# giraffevolvo.net
KiCad netlist of a schematic drawn in EAGLE
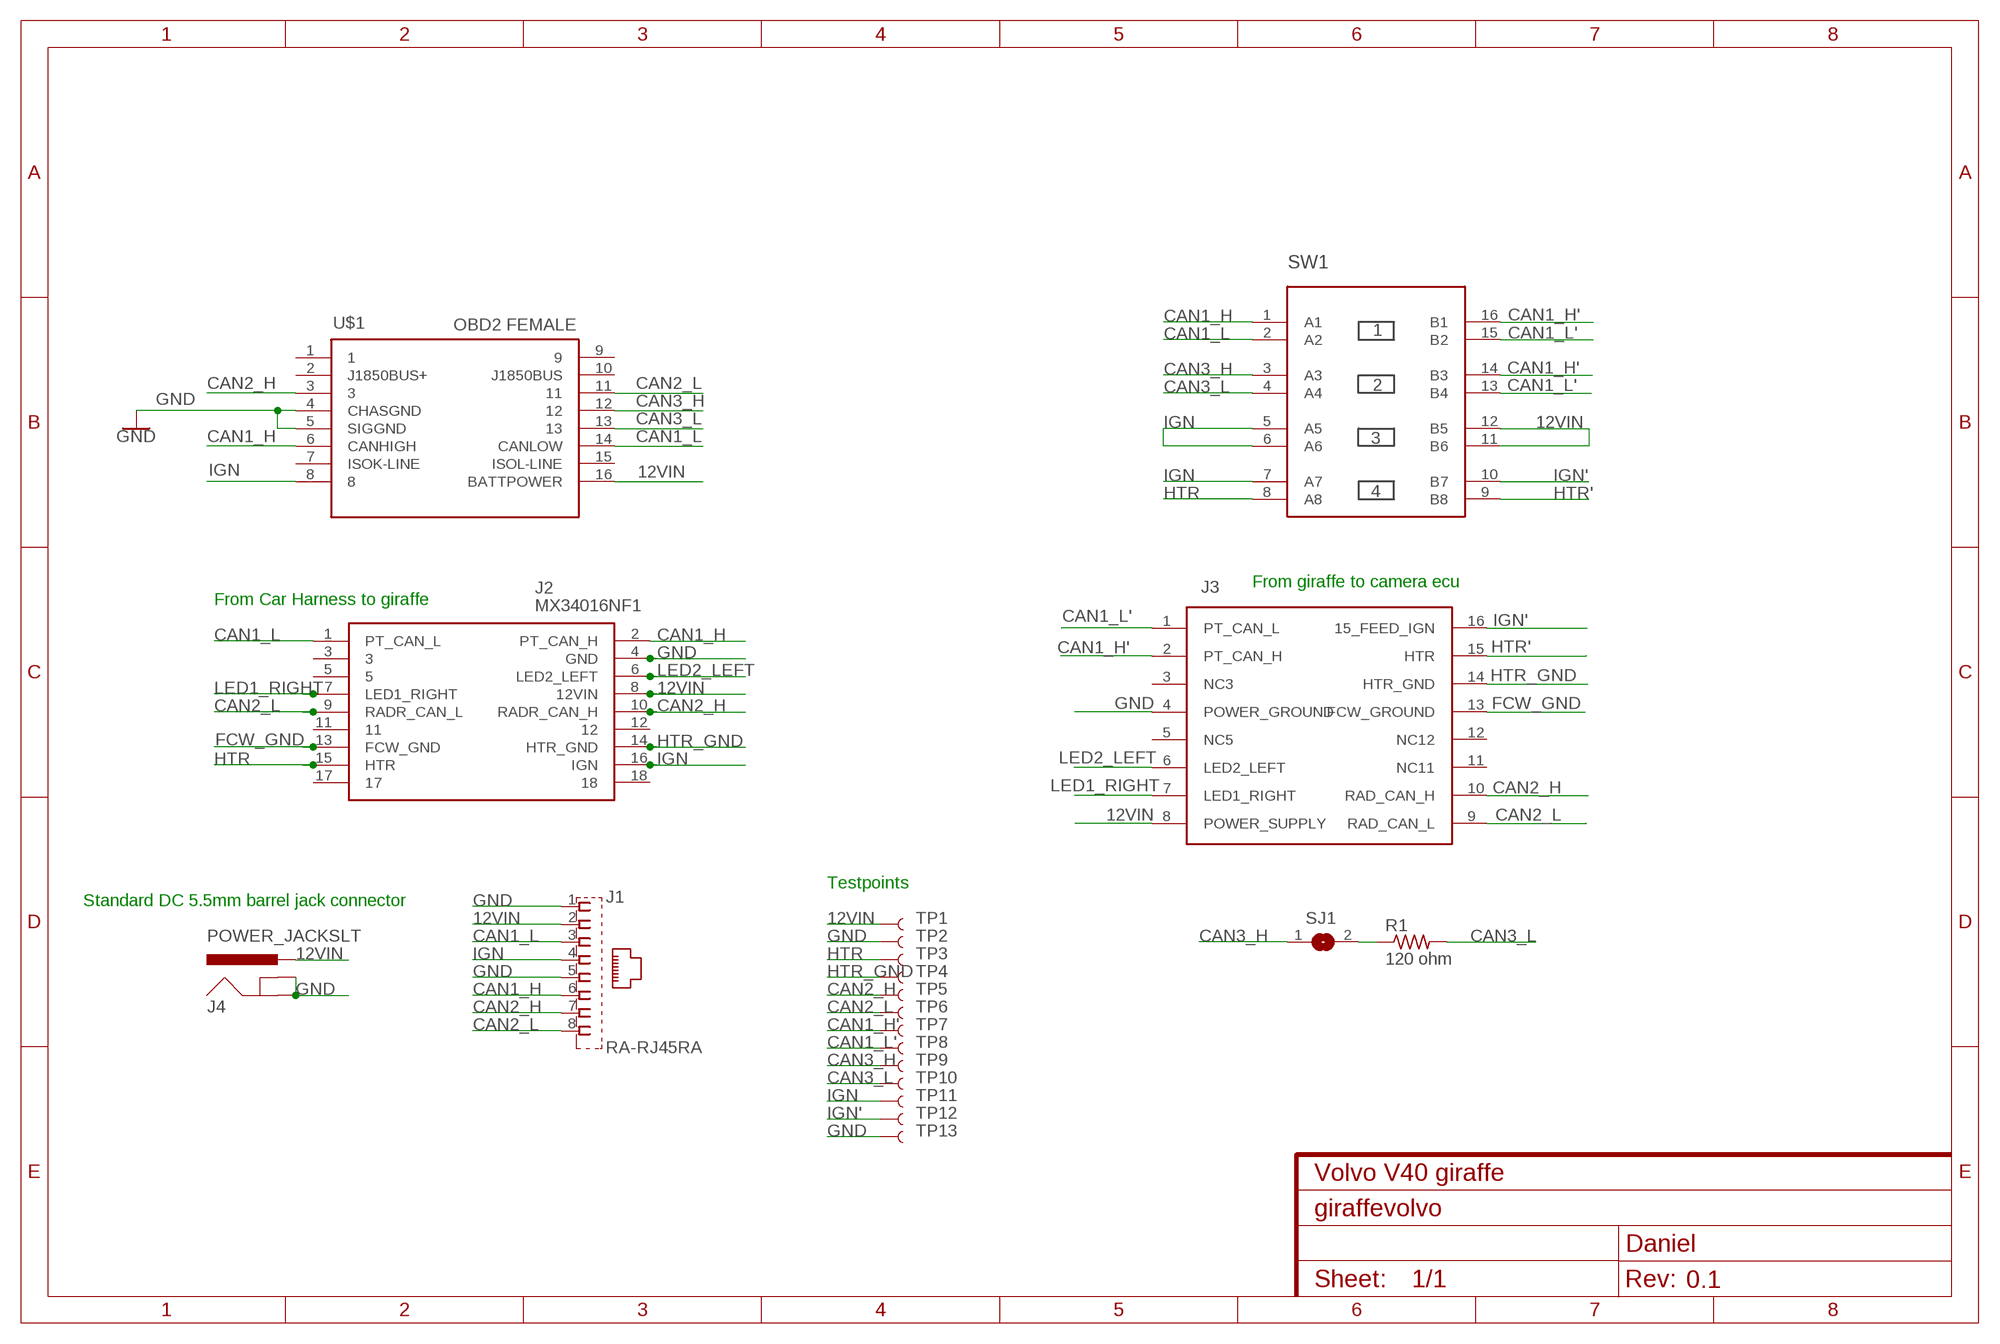
[diagram p0: schematic, sheet 1]

(export (version "E")
  (design (tool "Eeschema 10.0.6"))
  (components
    (comp (ref "J1")
      (value "RA-RJ45RA")
      (footprint "eagle-import:RA-RJ45")
      (libsource (lib "eagle-import") (part "RA-RJ45RA"))
    )
    (comp (ref "J2")
      (value "MX34016NF1")
      (footprint "eagle-import:MX34016NF1")
      (fields (field (name "MOUSER_PART_NUMBER") "656-MX34016NF1"))
      (libsource (lib "eagle-import") (part "MX34016NF1"))
    )
    (comp (ref "J3")
      (value "MX34016SF1")
      (footprint "eagle-import:MX34016SF1")
      (libsource (lib "eagle-import") (part "MX34016SF1"))
    )
    (comp (ref "J4")
      (value "POWER_JACKSLT")
      (footprint "eagle-import:POWER_JACK_SLOT")
      (libsource (lib "eagle-import") (part "POWER_JACKSLT"))
    )
    (comp (ref "R1")
      (value "120 ohm")
      (footprint "eagle-import:0603-R")
      (libsource (lib "eagle-import") (part "R0603"))
    )
    (comp (ref "SJ1") (value "SJ") (footprint "eagle-import:SJ") (libsource (lib "eagle-import") (part "SJ")))
    (comp (ref "SW1")
      (value "4XDPSTSMT")
      (footprint "eagle-import:4-DPST")
      (libsource (lib "eagle-import") (part "4XDPSTSMT"))
    )
    (comp (ref "TP1")
      (value "TEST-POINT2")
      (footprint "eagle-import:PAD.02X.02")
      (libsource (lib "eagle-import") (part "TEST-POINT2"))
    )
    (comp (ref "TP2")
      (value "TEST-POINT2")
      (footprint "eagle-import:PAD.02X.02")
      (libsource (lib "eagle-import") (part "TEST-POINT2"))
    )
    (comp (ref "TP3")
      (value "TEST-POINT2")
      (footprint "eagle-import:PAD.02X.02")
      (libsource (lib "eagle-import") (part "TEST-POINT2"))
    )
    (comp (ref "TP4")
      (value "TEST-POINT2")
      (footprint "eagle-import:PAD.02X.02")
      (libsource (lib "eagle-import") (part "TEST-POINT2"))
    )
    (comp (ref "TP5")
      (value "TEST-POINT2")
      (footprint "eagle-import:PAD.02X.02")
      (libsource (lib "eagle-import") (part "TEST-POINT2"))
    )
    (comp (ref "TP6")
      (value "TEST-POINT2")
      (footprint "eagle-import:PAD.02X.02")
      (libsource (lib "eagle-import") (part "TEST-POINT2"))
    )
    (comp (ref "TP7")
      (value "TEST-POINT2")
      (footprint "eagle-import:PAD.02X.02")
      (libsource (lib "eagle-import") (part "TEST-POINT2"))
    )
    (comp (ref "TP8")
      (value "TEST-POINT2")
      (footprint "eagle-import:PAD.02X.02")
      (libsource (lib "eagle-import") (part "TEST-POINT2"))
    )
    (comp (ref "TP9")
      (value "TEST-POINT2")
      (footprint "eagle-import:PAD.02X.02")
      (libsource (lib "eagle-import") (part "TEST-POINT2"))
    )
    (comp (ref "TP10")
      (value "TEST-POINT2")
      (footprint "eagle-import:PAD.02X.02")
      (libsource (lib "eagle-import") (part "TEST-POINT2"))
    )
    (comp (ref "TP11")
      (value "TEST-POINT2")
      (footprint "eagle-import:PAD.02X.02")
      (libsource (lib "eagle-import") (part "TEST-POINT2"))
    )
    (comp (ref "TP12")
      (value "TEST-POINT2")
      (footprint "eagle-import:PAD.02X.02")
      (libsource (lib "eagle-import") (part "TEST-POINT2"))
    )
    (comp (ref "TP13")
      (value "TEST-POINT2")
      (footprint "eagle-import:PAD.02X.02")
      (libsource (lib "eagle-import") (part "TEST-POINT2"))
    )
    (comp (ref "U$1")
      (value "OBDIIFEMALE")
      (footprint "eagle-import:OBDII-FEMALE")
      (fields (field (name "TEXT") "OBD2 FEMALE  "))
      (libsource (lib "eagle-import") (part "OBDIIFEMALE"))
    )
  )
  (nets
    (net (code "1") (name "/12VIN") (class "Default")
      (node (ref "J1") (pin "2") (pinfunction "2_2") (pintype "passive"))
      (node (ref "J2") (pin "8") (pinfunction "12VIN_8") (pintype "bidirectional"))
      (node (ref "J3") (pin "8") (pinfunction "POWER_SUPPLY_8") (pintype "power_in"))
      (node (ref "J4") (pin "PWR") (pinfunction "PWR_PWR") (pintype "bidirectional"))
      (node (ref "SW1") (pin "11") (pinfunction "B6_11") (pintype "bidirectional"))
      (node (ref "SW1") (pin "12") (pinfunction "B5_12") (pintype "bidirectional"))
      (node (ref "TP1") (pin "P$1") (pinfunction "1_P$1") (pintype "bidirectional"))
      (node (ref "U$1") (pin "16") (pinfunction "BATTPOWER_16") (pintype "bidirectional"))
    )
    (net (code "2") (name "/CAN1_H") (class "Default")
      (node (ref "J1") (pin "6") (pinfunction "6_6") (pintype "passive"))
      (node (ref "J2") (pin "2") (pinfunction "PT_CAN_H_2") (pintype "bidirectional"))
      (node (ref "SW1") (pin "1") (pinfunction "A1_1") (pintype "bidirectional"))
      (node (ref "U$1") (pin "6") (pinfunction "CANHIGH_6") (pintype "bidirectional"))
    )
    (net (code "3") (name "/CAN1_H'") (class "Default")
      (node (ref "J3") (pin "2") (pinfunction "PT_CAN_H_2") (pintype "bidirectional"))
      (node (ref "SW1") (pin "14") (pinfunction "B3_14") (pintype "bidirectional"))
      (node (ref "SW1") (pin "16") (pinfunction "B1_16") (pintype "bidirectional"))
      (node (ref "TP7") (pin "P$1") (pinfunction "1_P$1") (pintype "bidirectional"))
    )
    (net (code "4") (name "/CAN1_L") (class "Default")
      (node (ref "J1") (pin "3") (pinfunction "3_3") (pintype "passive"))
      (node (ref "J2") (pin "1") (pinfunction "PT_CAN_L_1") (pintype "bidirectional"))
      (node (ref "SW1") (pin "2") (pinfunction "A2_2") (pintype "bidirectional"))
      (node (ref "U$1") (pin "14") (pinfunction "CANLOW_14") (pintype "bidirectional"))
    )
    (net (code "5") (name "/CAN1_L'") (class "Default")
      (node (ref "J3") (pin "1") (pinfunction "PT_CAN_L_1") (pintype "bidirectional"))
      (node (ref "SW1") (pin "13") (pinfunction "B4_13") (pintype "bidirectional"))
      (node (ref "SW1") (pin "15") (pinfunction "B2_15") (pintype "bidirectional"))
      (node (ref "TP8") (pin "P$1") (pinfunction "1_P$1") (pintype "bidirectional"))
    )
    (net (code "6") (name "/CAN2_H") (class "Default")
      (node (ref "J1") (pin "7") (pinfunction "7_7") (pintype "passive"))
      (node (ref "J2") (pin "10") (pinfunction "RADR_CAN_H_10") (pintype "bidirectional"))
      (node (ref "J3") (pin "10") (pinfunction "RAD_CAN_H_10") (pintype "bidirectional"))
      (node (ref "TP5") (pin "P$1") (pinfunction "1_P$1") (pintype "bidirectional"))
      (node (ref "U$1") (pin "3") (pinfunction "3_3") (pintype "bidirectional"))
    )
    (net (code "7") (name "/CAN2_L") (class "Default")
      (node (ref "J1") (pin "8") (pinfunction "8_8") (pintype "passive"))
      (node (ref "J2") (pin "9") (pinfunction "RADR_CAN_L_9") (pintype "bidirectional"))
      (node (ref "J3") (pin "9") (pinfunction "RAD_CAN_L_9") (pintype "bidirectional"))
      (node (ref "TP6") (pin "P$1") (pinfunction "1_P$1") (pintype "bidirectional"))
      (node (ref "U$1") (pin "11") (pinfunction "11_11") (pintype "bidirectional"))
    )
    (net (code "8") (name "/CAN3_H") (class "Default")
      (node (ref "SJ1") (pin "1") (pinfunction "1_1") (pintype "passive"))
      (node (ref "SW1") (pin "3") (pinfunction "A3_3") (pintype "bidirectional"))
      (node (ref "TP9") (pin "P$1") (pinfunction "1_P$1") (pintype "bidirectional"))
      (node (ref "U$1") (pin "12") (pinfunction "12_12") (pintype "bidirectional"))
    )
    (net (code "9") (name "/CAN3_L") (class "Default")
      (node (ref "R1") (pin "2") (pinfunction "2_2") (pintype "passive"))
      (node (ref "SW1") (pin "4") (pinfunction "A4_4") (pintype "bidirectional"))
      (node (ref "TP10") (pin "P$1") (pinfunction "1_P$1") (pintype "bidirectional"))
      (node (ref "U$1") (pin "13") (pinfunction "13_13") (pintype "bidirectional"))
    )
    (net (code "10") (name "/FCW_GND") (class "Default")
      (node (ref "J2") (pin "13") (pinfunction "FCW_GND_13") (pintype "bidirectional"))
      (node (ref "J3") (pin "13") (pinfunction "FCW_GROUND_13") (pintype "bidirectional"))
    )
    (net (code "11") (name "/HTR") (class "Default")
      (node (ref "J2") (pin "15") (pinfunction "HTR_15") (pintype "bidirectional"))
      (node (ref "SW1") (pin "8") (pinfunction "A8_8") (pintype "bidirectional"))
      (node (ref "TP3") (pin "P$1") (pinfunction "1_P$1") (pintype "bidirectional"))
    )
    (net (code "12") (name "/HTR'") (class "Default")
      (node (ref "J3") (pin "15") (pinfunction "HTR_15") (pintype "bidirectional"))
      (node (ref "SW1") (pin "9") (pinfunction "B8_9") (pintype "bidirectional"))
    )
    (net (code "13") (name "/HTR_GND") (class "Default")
      (node (ref "J2") (pin "14") (pinfunction "HTR_GND_14") (pintype "bidirectional"))
      (node (ref "J3") (pin "14") (pinfunction "HTR_GND_14") (pintype "bidirectional"))
      (node (ref "TP4") (pin "P$1") (pinfunction "1_P$1") (pintype "bidirectional"))
    )
    (net (code "14") (name "/IGN") (class "Default")
      (node (ref "J1") (pin "4") (pinfunction "4_4") (pintype "passive"))
      (node (ref "J2") (pin "16") (pinfunction "IGN_16") (pintype "bidirectional"))
      (node (ref "SW1") (pin "5") (pinfunction "A5_5") (pintype "bidirectional"))
      (node (ref "SW1") (pin "6") (pinfunction "A6_6") (pintype "bidirectional"))
      (node (ref "SW1") (pin "7") (pinfunction "A7_7") (pintype "bidirectional"))
      (node (ref "TP11") (pin "P$1") (pinfunction "1_P$1") (pintype "bidirectional"))
      (node (ref "U$1") (pin "8") (pinfunction "8_8") (pintype "bidirectional"))
    )
    (net (code "15") (name "/IGN'") (class "Default")
      (node (ref "J3") (pin "16") (pinfunction "15_FEED_IGN_16") (pintype "bidirectional"))
      (node (ref "SW1") (pin "10") (pinfunction "B7_10") (pintype "bidirectional"))
      (node (ref "TP12") (pin "P$1") (pinfunction "1_P$1") (pintype "bidirectional"))
    )
    (net (code "16") (name "/LED1_RIGHT") (class "Default")
      (node (ref "J2") (pin "7") (pinfunction "LED1_RIGHT_7") (pintype "bidirectional"))
      (node (ref "J3") (pin "7") (pinfunction "LED1_RIGHT_7") (pintype "bidirectional"))
    )
    (net (code "17") (name "/LED2_LEFT") (class "Default")
      (node (ref "J2") (pin "6") (pinfunction "LED2_LEFT_6") (pintype "bidirectional"))
      (node (ref "J3") (pin "6") (pinfunction "LED2_LEFT_6") (pintype "bidirectional"))
    )
    (net (code "18") (name "GND") (class "Default")
      (node (ref "J1") (pin "1") (pinfunction "1_1") (pintype "passive"))
      (node (ref "J1") (pin "5") (pinfunction "5_5") (pintype "passive"))
      (node (ref "J2") (pin "4") (pinfunction "GND_4") (pintype "bidirectional"))
      (node (ref "J3") (pin "4") (pinfunction "POWER_GROUND_4") (pintype "bidirectional"))
      (node (ref "J4") (pin "GND@1") (pinfunction "GNDBREAK_GND@1") (pintype "bidirectional"))
      (node (ref "J4") (pin "GND@2") (pinfunction "GND_GND@2") (pintype "bidirectional"))
      (node (ref "TP13") (pin "P$1") (pinfunction "1_P$1") (pintype "bidirectional"))
      (node (ref "TP2") (pin "P$1") (pinfunction "1_P$1") (pintype "bidirectional"))
      (node (ref "U$1") (pin "4") (pinfunction "CHASGND_4") (pintype "bidirectional"))
      (node (ref "U$1") (pin "5") (pinfunction "SIGGND_5") (pintype "bidirectional"))
    )
    (net (code "19") (name "Net-(R1-Pad1)") (class "Default")
      (node (ref "R1") (pin "1") (pinfunction "1_1") (pintype "passive"))
      (node (ref "SJ1") (pin "2") (pinfunction "2_2") (pintype "passive"))
    )
    (net (code "20") (name "unconnected-(J2-Pad3)") (class "Default")
      (node (ref "J2") (pin "3") (pinfunction "3_3") (pintype "no_connect"))
    )
    (net (code "21") (name "unconnected-(J2-Pad5)") (class "Default")
      (node (ref "J2") (pin "5") (pinfunction "5_5") (pintype "no_connect"))
    )
    (net (code "22") (name "unconnected-(J2-Pad11)") (class "Default")
      (node (ref "J2") (pin "11") (pinfunction "11_11") (pintype "no_connect"))
    )
    (net (code "23") (name "unconnected-(J2-Pad12)") (class "Default")
      (node (ref "J2") (pin "12") (pinfunction "12_12") (pintype "no_connect"))
    )
    (net (code "24") (name "unconnected-(J2-Pad17)") (class "Default")
      (node (ref "J2") (pin "17") (pinfunction "17_17") (pintype "no_connect"))
    )
    (net (code "25") (name "unconnected-(J2-Pad18)") (class "Default")
      (node (ref "J2") (pin "18") (pinfunction "18_18") (pintype "no_connect"))
    )
    (net (code "26") (name "unconnected-(J3-NC3-Pad3)") (class "Default")
      (node (ref "J3") (pin "3") (pinfunction "NC3_3") (pintype "no_connect"))
    )
    (net (code "27") (name "unconnected-(J3-NC5-Pad5)") (class "Default")
      (node (ref "J3") (pin "5") (pinfunction "NC5_5") (pintype "no_connect"))
    )
    (net (code "28") (name "unconnected-(J3-NC11-Pad11)") (class "Default")
      (node (ref "J3") (pin "11") (pinfunction "NC11_11") (pintype "no_connect"))
    )
    (net (code "29") (name "unconnected-(J3-NC12-Pad12)") (class "Default")
      (node (ref "J3") (pin "12") (pinfunction "NC12_12") (pintype "no_connect"))
    )
    (net (code "30") (name "unconnected-(U$1-ISOK-LINE-Pad7)") (class "Default")
      (node (ref "U$1") (pin "7") (pinfunction "ISOK-LINE_7") (pintype "bidirectional"))
    )
    (net (code "31") (name "unconnected-(U$1-ISOL-LINE-Pad15)") (class "Default")
      (node (ref "U$1") (pin "15") (pinfunction "ISOL-LINE_15") (pintype "bidirectional"))
    )
    (net (code "32") (name "unconnected-(U$1-J1850BUS+-Pad2)") (class "Default")
      (node (ref "U$1") (pin "2") (pinfunction "J1850BUS+_2") (pintype "bidirectional"))
    )
    (net (code "33") (name "unconnected-(U$1-J1850BUS-Pad10)") (class "Default")
      (node (ref "U$1") (pin "10") (pinfunction "J1850BUS_10") (pintype "bidirectional"))
    )
    (net (code "34") (name "unconnected-(U$1-Pad1)") (class "Default")
      (node (ref "U$1") (pin "1") (pinfunction "1_1") (pintype "bidirectional"))
    )
    (net (code "35") (name "unconnected-(U$1-Pad9)") (class "Default")
      (node (ref "U$1") (pin "9") (pinfunction "9_9") (pintype "bidirectional"))
    )
  )
)
